# M306B.net
KiCad netlist of a schematic drawn in EAGLE
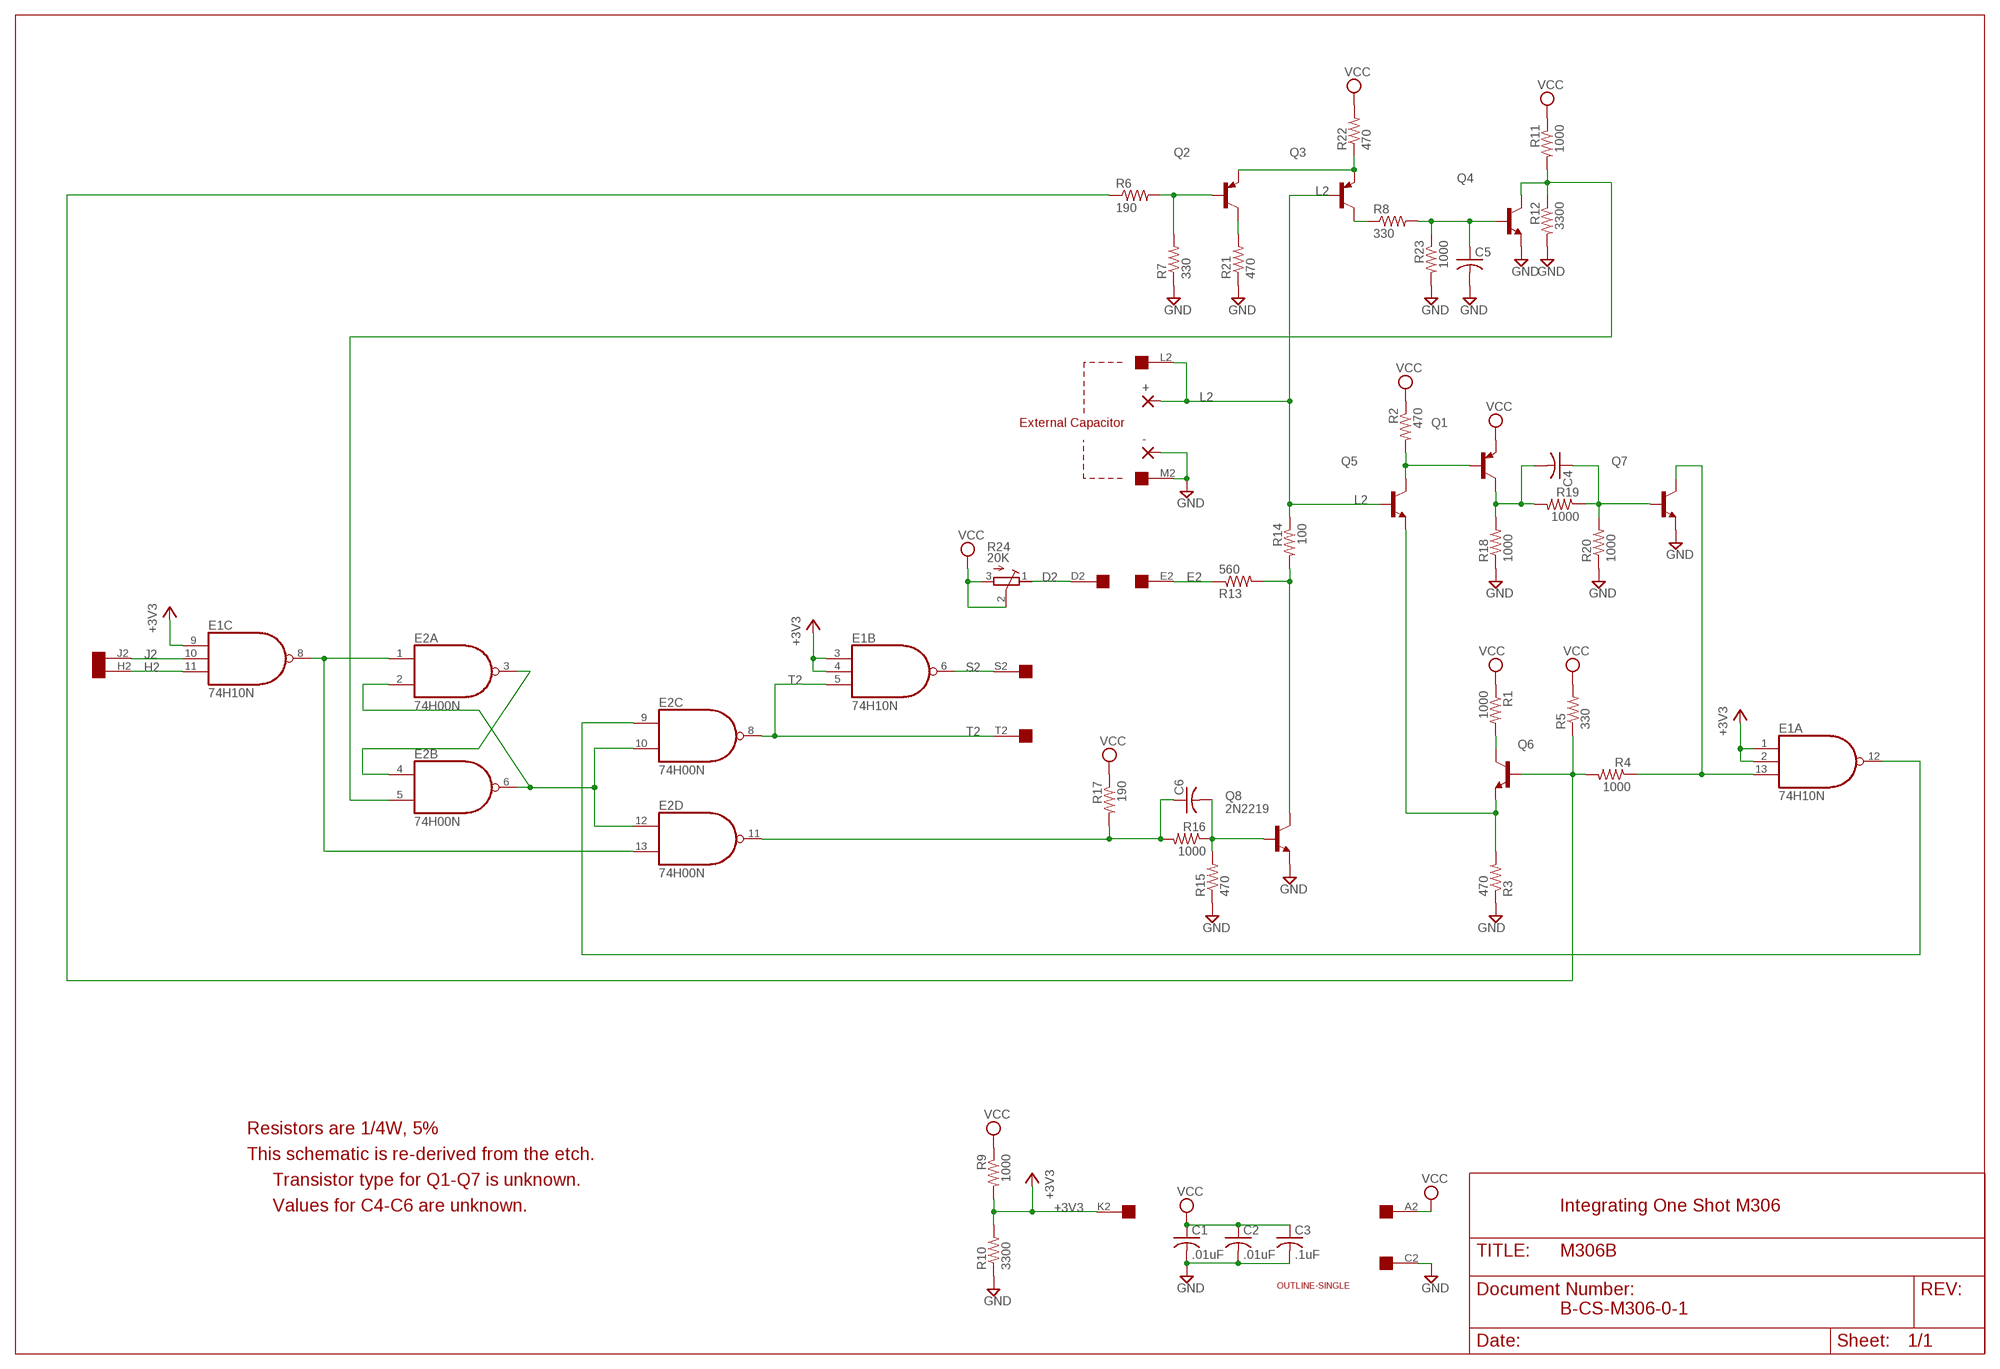
[diagram p0: schematic, sheet 1]

(export (version "E")
  (design (tool "Eeschema 10.0.6"))
  (components
    (comp (ref "+")
      (value "3,17/1,3")
      (footprint "eagle-import:3,17_1,3")
      (libsource (lib "eagle-import") (part "3,17/1,3"))
    )
    (comp (ref "-")
      (value "3,17/1,3")
      (footprint "eagle-import:3,17_1,3")
      (libsource (lib "eagle-import") (part "3,17/1,3"))
    )
    (comp (ref "C1")
      (value ".01uF")
      (footprint "eagle-import:C050-025X075")
      (libsource (lib "eagle-import") (part "C-US050-025X075"))
    )
    (comp (ref "C2")
      (value ".01uF")
      (footprint "eagle-import:C050-025X075")
      (libsource (lib "eagle-import") (part "C-US050-025X075"))
    )
    (comp (ref "C3")
      (value ".1uF")
      (footprint "eagle-import:C102-043X133")
      (libsource (lib "eagle-import") (part "C-US102-043X133"))
    )
    (comp (ref "C4")
      (value "C-US075-032X103")
      (footprint "eagle-import:C075-032X103")
      (libsource (lib "eagle-import") (part "C-US075-032X103"))
    )
    (comp (ref "C5")
      (value "C-US075-032X103")
      (footprint "eagle-import:C075-032X103")
      (libsource (lib "eagle-import") (part "C-US075-032X103"))
    )
    (comp (ref "C6")
      (value "C-US075-032X103")
      (footprint "eagle-import:C075-032X103")
      (libsource (lib "eagle-import") (part "C-US075-032X103"))
    )
    (comp (ref "E1")
      (value "74H10N")
      (footprint "eagle-import:DIL14")
      (libsource (lib "eagle-import") (part "7410N"))
    )
    (comp (ref "E2")
      (value "74H00N")
      (footprint "eagle-import:DIL14")
      (libsource (lib "eagle-import") (part "7400N"))
    )
    (comp (ref "Q1")
      (value "-PNP-TO5")
      (footprint "eagle-import:TO5")
      (libsource (lib "eagle-import") (part "-PNP-TO5"))
    )
    (comp (ref "Q2")
      (value "-PNP-TO5")
      (footprint "eagle-import:TO5")
      (libsource (lib "eagle-import") (part "-PNP-TO5"))
    )
    (comp (ref "Q3")
      (value "-PNP-TO5")
      (footprint "eagle-import:TO5")
      (libsource (lib "eagle-import") (part "-PNP-TO5"))
    )
    (comp (ref "Q4")
      (value "2N3019-NPN-TO39-EBC")
      (footprint "eagle-import:TO39")
      (libsource (lib "eagle-import") (part "-NPN-TO39-EBC2N3019"))
    )
    (comp (ref "Q5")
      (value "2N3019-NPN-TO39-EBC")
      (footprint "eagle-import:TO39")
      (libsource (lib "eagle-import") (part "-NPN-TO39-EBC2N3019"))
    )
    (comp (ref "Q6")
      (value "2N3019-NPN-TO39-EBC")
      (footprint "eagle-import:TO39")
      (libsource (lib "eagle-import") (part "-NPN-TO39-EBC2N3019"))
    )
    (comp (ref "Q7")
      (value "2N3019-NPN-TO39-EBC")
      (footprint "eagle-import:TO39")
      (libsource (lib "eagle-import") (part "-NPN-TO39-EBC2N3019"))
    )
    (comp (ref "Q8")
      (value "2N2219")
      (footprint "eagle-import:TO5")
      (libsource (lib "eagle-import") (part "2N2219"))
    )
    (comp (ref "R1")
      (value "1000")
      (footprint "eagle-import:0207_10")
      (libsource (lib "eagle-import") (part "R-US_0207/10"))
    )
    (comp (ref "R2")
      (value "470")
      (footprint "eagle-import:0207_10")
      (libsource (lib "eagle-import") (part "R-US_0207/10"))
    )
    (comp (ref "R3")
      (value "470")
      (footprint "eagle-import:0207_10")
      (libsource (lib "eagle-import") (part "R-US_0207/10"))
    )
    (comp (ref "R4")
      (value "1000")
      (footprint "eagle-import:0207_10")
      (libsource (lib "eagle-import") (part "R-US_0207/10"))
    )
    (comp (ref "R5")
      (value "330")
      (footprint "eagle-import:0207_10")
      (libsource (lib "eagle-import") (part "R-US_0207/10"))
    )
    (comp (ref "R6")
      (value "190")
      (footprint "eagle-import:0207_10")
      (libsource (lib "eagle-import") (part "R-US_0207/10"))
    )
    (comp (ref "R7")
      (value "330")
      (footprint "eagle-import:0207_10")
      (libsource (lib "eagle-import") (part "R-US_0207/10"))
    )
    (comp (ref "R8")
      (value "330")
      (footprint "eagle-import:0207_10")
      (libsource (lib "eagle-import") (part "R-US_0207/10"))
    )
    (comp (ref "R9")
      (value "1000")
      (footprint "eagle-import:0207_10")
      (libsource (lib "eagle-import") (part "R-US_0207/10"))
    )
    (comp (ref "R10")
      (value "3300")
      (footprint "eagle-import:0207_10")
      (libsource (lib "eagle-import") (part "R-US_0207/10"))
    )
    (comp (ref "R11")
      (value "1000")
      (footprint "eagle-import:0207_10")
      (libsource (lib "eagle-import") (part "R-US_0207/10"))
    )
    (comp (ref "R12")
      (value "3300")
      (footprint "eagle-import:0207_10")
      (libsource (lib "eagle-import") (part "R-US_0207/10"))
    )
    (comp (ref "R13")
      (value "560")
      (footprint "eagle-import:0207_10")
      (libsource (lib "eagle-import") (part "R-US_0207/10"))
    )
    (comp (ref "R14")
      (value "100")
      (footprint "eagle-import:0207_10")
      (libsource (lib "eagle-import") (part "R-US_0207/10"))
    )
    (comp (ref "R15")
      (value "470")
      (footprint "eagle-import:0207_10")
      (libsource (lib "eagle-import") (part "R-US_0207/10"))
    )
    (comp (ref "R16")
      (value "1000")
      (footprint "eagle-import:0207_10")
      (libsource (lib "eagle-import") (part "R-US_0207/10"))
    )
    (comp (ref "R17")
      (value "190")
      (footprint "eagle-import:0207_10")
      (libsource (lib "eagle-import") (part "R-US_0207/10"))
    )
    (comp (ref "R18")
      (value "1000")
      (footprint "eagle-import:0207_10")
      (libsource (lib "eagle-import") (part "R-US_0207/10"))
    )
    (comp (ref "R19")
      (value "1000")
      (footprint "eagle-import:0207_10")
      (libsource (lib "eagle-import") (part "R-US_0207/10"))
    )
    (comp (ref "R20")
      (value "1000")
      (footprint "eagle-import:0207_10")
      (libsource (lib "eagle-import") (part "R-US_0207/10"))
    )
    (comp (ref "R21")
      (value "470")
      (footprint "eagle-import:0207_10")
      (libsource (lib "eagle-import") (part "R-US_0207/10"))
    )
    (comp (ref "R22")
      (value "470")
      (footprint "eagle-import:0207_10")
      (libsource (lib "eagle-import") (part "R-US_0207/10"))
    )
    (comp (ref "R23")
      (value "1000")
      (footprint "eagle-import:0207_10")
      (libsource (lib "eagle-import") (part "R-US_0207/10"))
    )
    (comp (ref "R24")
      (value "20K")
      (footprint "eagle-import:3006Y")
      (libsource (lib "eagle-import") (part "275P"))
    )
    (comp (ref "U$1")
      (value "SINGLE")
      (footprint "eagle-import:EDGE-CON2")
      (libsource (lib "eagle-import") (part "SINGLE"))
    )
    (comp (ref "U$2")
      (value "OUTLINE-SINGLE")
      (footprint "eagle-import:SINGLE")
      (libsource (lib "eagle-import") (part "OUTLINE-SINGLE"))
    )
  )
  (nets
    (net (code "1") (name "+3V3") (class "Default")
      (node (ref "E1") (pin "1") (pinfunction "I0_1") (pintype "input"))
      (node (ref "E1") (pin "2") (pinfunction "I1_2") (pintype "input"))
      (node (ref "E1") (pin "3") (pinfunction "I0_3") (pintype "input"))
      (node (ref "E1") (pin "4") (pinfunction "I1_4") (pintype "input"))
      (node (ref "E1") (pin "9") (pinfunction "I0_9") (pintype "input"))
      (node (ref "R10") (pin "2") (pinfunction "2_2") (pintype "passive"))
      (node (ref "R9") (pin "2") (pinfunction "2_2") (pintype "passive"))
      (node (ref "U$1") (pin "K2") (pinfunction "1_K2") (pintype "bidirectional"))
    )
    (net (code "2") (name "/D2") (class "Default")
      (node (ref "R24") (pin "1") (pinfunction "A_1") (pintype "passive"))
      (node (ref "U$1") (pin "D2") (pinfunction "1_D2") (pintype "bidirectional"))
    )
    (net (code "3") (name "/E2") (class "Default")
      (node (ref "R13") (pin "1") (pinfunction "1_1") (pintype "passive"))
      (node (ref "U$1") (pin "E2") (pinfunction "1_E2") (pintype "bidirectional"))
    )
    (net (code "4") (name "/H2") (class "Default")
      (node (ref "E1") (pin "11") (pinfunction "I2_11") (pintype "input"))
      (node (ref "U$1") (pin "H2") (pinfunction "1_H2") (pintype "bidirectional"))
    )
    (net (code "5") (name "/J2") (class "Default")
      (node (ref "E1") (pin "10") (pinfunction "I1_10") (pintype "input"))
      (node (ref "U$1") (pin "J2") (pinfunction "1_J2") (pintype "bidirectional"))
    )
    (net (code "6") (name "/L2") (class "Default")
      (node (ref "+") (pin "1") (pinfunction "P_1") (pintype "passive"))
      (node (ref "Q3") (pin "2") (pinfunction "B_2") (pintype "passive"))
      (node (ref "Q5") (pin "2") (pinfunction "B_2") (pintype "passive"))
      (node (ref "R14") (pin "1") (pinfunction "1_1") (pintype "passive"))
      (node (ref "U$1") (pin "L2") (pinfunction "1_L2") (pintype "bidirectional"))
    )
    (net (code "7") (name "/S2") (class "Default")
      (node (ref "E1") (pin "6") (pinfunction "O_6") (pintype "output"))
      (node (ref "U$1") (pin "S2") (pinfunction "1_S2") (pintype "bidirectional"))
    )
    (net (code "8") (name "/T2") (class "Default")
      (node (ref "E1") (pin "5") (pinfunction "I2_5") (pintype "input"))
      (node (ref "E2") (pin "8") (pinfunction "O_8") (pintype "output"))
      (node (ref "U$1") (pin "T2") (pinfunction "1_T2") (pintype "bidirectional"))
    )
    (net (code "9") (name "GND") (class "Default")
      (node (ref "-") (pin "1") (pinfunction "P_1") (pintype "passive"))
      (node (ref "C1") (pin "2") (pinfunction "2_2") (pintype "passive"))
      (node (ref "C2") (pin "2") (pinfunction "2_2") (pintype "passive"))
      (node (ref "C3") (pin "2") (pinfunction "2_2") (pintype "passive"))
      (node (ref "C5") (pin "2") (pinfunction "2_2") (pintype "passive"))
      (node (ref "Q4") (pin "1") (pinfunction "E_1") (pintype "passive"))
      (node (ref "Q7") (pin "1") (pinfunction "E_1") (pintype "passive"))
      (node (ref "Q8") (pin "1") (pinfunction "E_1") (pintype "passive"))
      (node (ref "R10") (pin "1") (pinfunction "1_1") (pintype "passive"))
      (node (ref "R12") (pin "2") (pinfunction "2_2") (pintype "passive"))
      (node (ref "R15") (pin "1") (pinfunction "1_1") (pintype "passive"))
      (node (ref "R18") (pin "1") (pinfunction "1_1") (pintype "passive"))
      (node (ref "R20") (pin "1") (pinfunction "1_1") (pintype "passive"))
      (node (ref "R21") (pin "1") (pinfunction "1_1") (pintype "passive"))
      (node (ref "R23") (pin "2") (pinfunction "2_2") (pintype "passive"))
      (node (ref "R3") (pin "1") (pinfunction "1_1") (pintype "passive"))
      (node (ref "R7") (pin "1") (pinfunction "1_1") (pintype "passive"))
      (node (ref "U$1") (pin "C2") (pinfunction "1_C2") (pintype "bidirectional"))
      (node (ref "U$1") (pin "M2") (pinfunction "1_M2") (pintype "bidirectional"))
    )
    (net (code "10") (name "Net-(E1A-I2)") (class "Default")
      (node (ref "E1") (pin "13") (pinfunction "I2_13") (pintype "input"))
      (node (ref "Q7") (pin "3") (pinfunction "C_3") (pintype "passive"))
      (node (ref "R4") (pin "1") (pinfunction "1_1") (pintype "passive"))
    )
    (net (code "11") (name "Net-(E1A-O)") (class "Default")
      (node (ref "E1") (pin "12") (pinfunction "O_12") (pintype "output"))
      (node (ref "E2") (pin "9") (pinfunction "I0_9") (pintype "input"))
    )
    (net (code "12") (name "Net-(E1C-O)") (class "Default")
      (node (ref "E1") (pin "8") (pinfunction "O_8") (pintype "output"))
      (node (ref "E2") (pin "1") (pinfunction "I0_1") (pintype "input"))
      (node (ref "E2") (pin "13") (pinfunction "I1_13") (pintype "input"))
    )
    (net (code "13") (name "Net-(E2A-I1)") (class "Default")
      (node (ref "E2") (pin "10") (pinfunction "I1_10") (pintype "input"))
      (node (ref "E2") (pin "12") (pinfunction "I0_12") (pintype "input"))
      (node (ref "E2") (pin "2") (pinfunction "I1_2") (pintype "input"))
      (node (ref "E2") (pin "6") (pinfunction "O_6") (pintype "output"))
    )
    (net (code "14") (name "Net-(E2A-O)") (class "Default")
      (node (ref "E2") (pin "3") (pinfunction "O_3") (pintype "output"))
      (node (ref "E2") (pin "4") (pinfunction "I0_4") (pintype "input"))
    )
    (net (code "15") (name "Net-(E2B-I1)") (class "Default")
      (node (ref "E2") (pin "5") (pinfunction "I1_5") (pintype "input"))
      (node (ref "Q4") (pin "3") (pinfunction "C_3") (pintype "passive"))
      (node (ref "R11") (pin "2") (pinfunction "2_2") (pintype "passive"))
      (node (ref "R12") (pin "1") (pinfunction "1_1") (pintype "passive"))
    )
    (net (code "16") (name "Net-(E2D-O)") (class "Default")
      (node (ref "C6") (pin "1") (pinfunction "1_1") (pintype "passive"))
      (node (ref "E2") (pin "11") (pinfunction "O_11") (pintype "output"))
      (node (ref "R16") (pin "2") (pinfunction "2_2") (pintype "passive"))
      (node (ref "R17") (pin "2") (pinfunction "2_2") (pintype "passive"))
    )
    (net (code "17") (name "Net-(Q1-B)") (class "Default")
      (node (ref "Q1") (pin "2") (pinfunction "B_2") (pintype "passive"))
      (node (ref "Q5") (pin "3") (pinfunction "C_3") (pintype "passive"))
      (node (ref "R2") (pin "2") (pinfunction "2_2") (pintype "passive"))
    )
    (net (code "18") (name "Net-(Q1-C)") (class "Default")
      (node (ref "C4") (pin "2") (pinfunction "2_2") (pintype "passive"))
      (node (ref "Q1") (pin "3") (pinfunction "C_3") (pintype "passive"))
      (node (ref "R18") (pin "2") (pinfunction "2_2") (pintype "passive"))
      (node (ref "R19") (pin "2") (pinfunction "2_2") (pintype "passive"))
    )
    (net (code "19") (name "Net-(Q2-B)") (class "Default")
      (node (ref "Q2") (pin "2") (pinfunction "B_2") (pintype "passive"))
      (node (ref "R6") (pin "2") (pinfunction "2_2") (pintype "passive"))
      (node (ref "R7") (pin "2") (pinfunction "2_2") (pintype "passive"))
    )
    (net (code "20") (name "Net-(Q2-C)") (class "Default")
      (node (ref "Q2") (pin "3") (pinfunction "C_3") (pintype "passive"))
      (node (ref "R21") (pin "2") (pinfunction "2_2") (pintype "passive"))
    )
    (net (code "21") (name "Net-(Q2-E)") (class "Default")
      (node (ref "Q2") (pin "1") (pinfunction "E_1") (pintype "passive"))
      (node (ref "Q3") (pin "1") (pinfunction "E_1") (pintype "passive"))
      (node (ref "R22") (pin "1") (pinfunction "1_1") (pintype "passive"))
    )
    (net (code "22") (name "Net-(Q3-C)") (class "Default")
      (node (ref "Q3") (pin "3") (pinfunction "C_3") (pintype "passive"))
      (node (ref "R8") (pin "1") (pinfunction "1_1") (pintype "passive"))
    )
    (net (code "23") (name "Net-(Q4-B)") (class "Default")
      (node (ref "C5") (pin "1") (pinfunction "1_1") (pintype "passive"))
      (node (ref "Q4") (pin "2") (pinfunction "B_2") (pintype "passive"))
      (node (ref "R23") (pin "1") (pinfunction "1_1") (pintype "passive"))
      (node (ref "R8") (pin "2") (pinfunction "2_2") (pintype "passive"))
    )
    (net (code "24") (name "Net-(Q5-E)") (class "Default")
      (node (ref "Q5") (pin "1") (pinfunction "E_1") (pintype "passive"))
      (node (ref "Q6") (pin "1") (pinfunction "E_1") (pintype "passive"))
      (node (ref "R3") (pin "2") (pinfunction "2_2") (pintype "passive"))
    )
    (net (code "25") (name "Net-(Q6-B)") (class "Default")
      (node (ref "Q6") (pin "2") (pinfunction "B_2") (pintype "passive"))
      (node (ref "R4") (pin "2") (pinfunction "2_2") (pintype "passive"))
      (node (ref "R5") (pin "1") (pinfunction "1_1") (pintype "passive"))
      (node (ref "R6") (pin "1") (pinfunction "1_1") (pintype "passive"))
    )
    (net (code "26") (name "Net-(Q6-C)") (class "Default")
      (node (ref "Q6") (pin "3") (pinfunction "C_3") (pintype "passive"))
      (node (ref "R1") (pin "2") (pinfunction "2_2") (pintype "passive"))
    )
    (net (code "27") (name "Net-(Q7-B)") (class "Default")
      (node (ref "C4") (pin "1") (pinfunction "1_1") (pintype "passive"))
      (node (ref "Q7") (pin "2") (pinfunction "B_2") (pintype "passive"))
      (node (ref "R19") (pin "1") (pinfunction "1_1") (pintype "passive"))
      (node (ref "R20") (pin "2") (pinfunction "2_2") (pintype "passive"))
    )
    (net (code "28") (name "Net-(Q8-B)") (class "Default")
      (node (ref "C6") (pin "2") (pinfunction "2_2") (pintype "passive"))
      (node (ref "Q8") (pin "2") (pinfunction "B_2") (pintype "passive"))
      (node (ref "R15") (pin "2") (pinfunction "2_2") (pintype "passive"))
      (node (ref "R16") (pin "1") (pinfunction "1_1") (pintype "passive"))
    )
    (net (code "29") (name "Net-(Q8-C)") (class "Default")
      (node (ref "Q8") (pin "3") (pinfunction "C_3") (pintype "passive"))
      (node (ref "R13") (pin "2") (pinfunction "2_2") (pintype "passive"))
      (node (ref "R14") (pin "2") (pinfunction "2_2") (pintype "passive"))
    )
    (net (code "30") (name "VCC") (class "Default")
      (node (ref "C1") (pin "1") (pinfunction "1_1") (pintype "passive"))
      (node (ref "C2") (pin "1") (pinfunction "1_1") (pintype "passive"))
      (node (ref "C3") (pin "1") (pinfunction "1_1") (pintype "passive"))
      (node (ref "Q1") (pin "1") (pinfunction "E_1") (pintype "passive"))
      (node (ref "R1") (pin "1") (pinfunction "1_1") (pintype "passive"))
      (node (ref "R11") (pin "1") (pinfunction "1_1") (pintype "passive"))
      (node (ref "R17") (pin "1") (pinfunction "1_1") (pintype "passive"))
      (node (ref "R2") (pin "1") (pinfunction "1_1") (pintype "passive"))
      (node (ref "R22") (pin "2") (pinfunction "2_2") (pintype "passive"))
      (node (ref "R24") (pin "2") (pinfunction "S_2") (pintype "passive"))
      (node (ref "R24") (pin "3") (pinfunction "E_3") (pintype "passive"))
      (node (ref "R5") (pin "2") (pinfunction "2_2") (pintype "passive"))
      (node (ref "R9") (pin "1") (pinfunction "1_1") (pintype "passive"))
      (node (ref "U$1") (pin "A2") (pinfunction "1_A2") (pintype "bidirectional"))
    )
  )
)
